# uStar.net
KiCad netlist of a schematic drawn in EAGLE
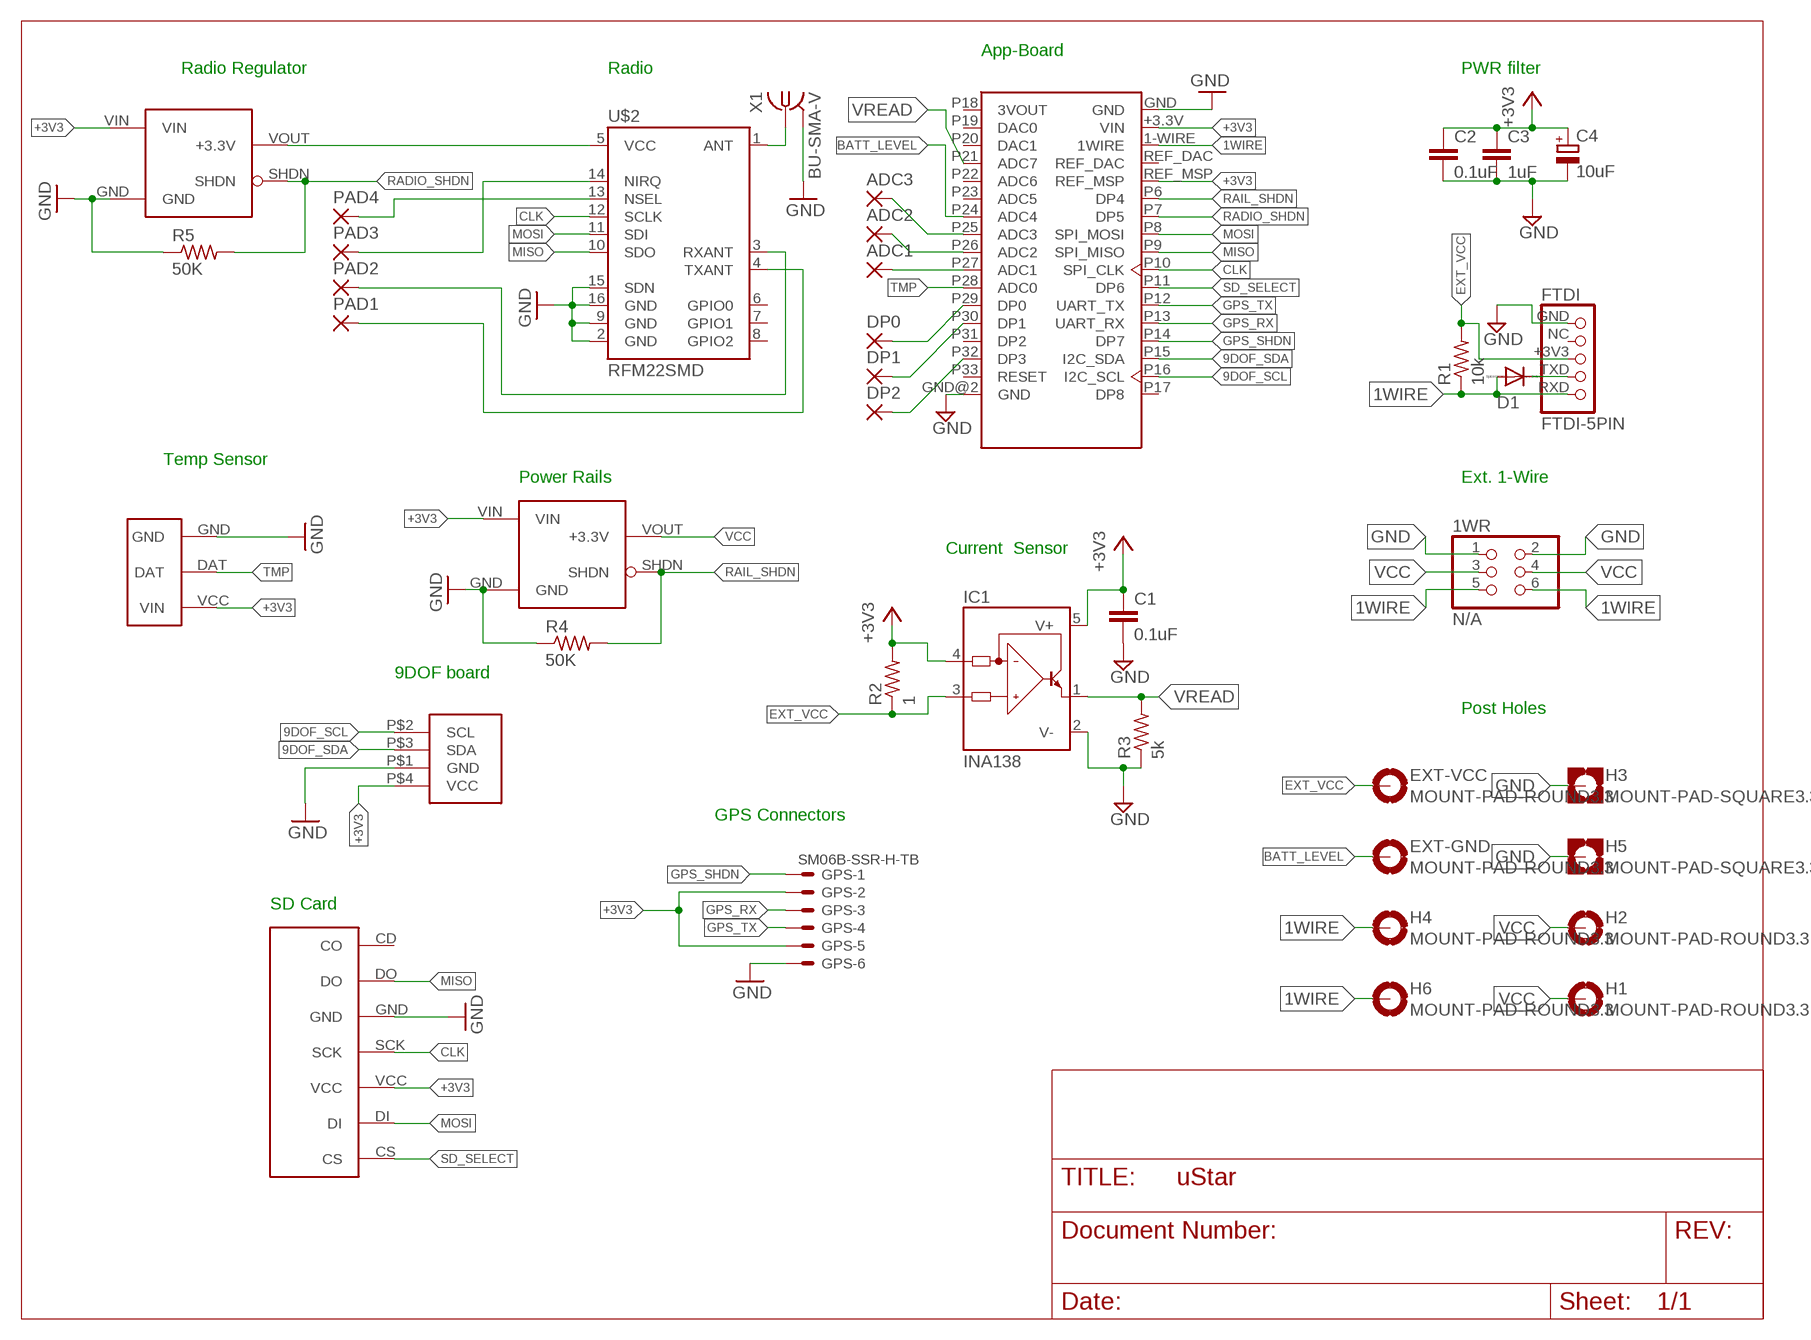
[diagram p0: schematic, sheet 1]

(export (version "E")
  (design (tool "Eeschema 10.0.6"))
  (components
    (comp (ref "1WR")
      (value "N/A")
      (footprint "eagle-import:2X03")
      (libsource (lib "eagle-import") (part "PINHD-2X3"))
    )
    (comp (ref "ADC1")
      (value "1,6/0,9")
      (footprint "eagle-import:1,6_0,9")
      (libsource (lib "eagle-import") (part "1,6/0,9"))
    )
    (comp (ref "ADC2")
      (value "1,6/0,9")
      (footprint "eagle-import:1,6_0,9")
      (libsource (lib "eagle-import") (part "1,6/0,9"))
    )
    (comp (ref "ADC3")
      (value "1,6/0,9")
      (footprint "eagle-import:1,6_0,9")
      (libsource (lib "eagle-import") (part "1,6/0,9"))
    )
    (comp (ref "C1")
      (value "0.1uF")
      (footprint "eagle-import:C0805")
      (libsource (lib "eagle-import") (part "C-EUC0805"))
    )
    (comp (ref "C2")
      (value "0.1uF")
      (footprint "eagle-import:C0603")
      (libsource (lib "eagle-import") (part "C-EUC0603"))
    )
    (comp (ref "C3")
      (value "1uF")
      (footprint "eagle-import:C0603")
      (libsource (lib "eagle-import") (part "C-EUC0603"))
    )
    (comp (ref "C4")
      (value "10uF")
      (footprint "eagle-import:SMC_B")
      (libsource (lib "eagle-import") (part "CPOL-EUSMCB"))
    )
    (comp (ref "D1")
      (value "1N4148DO35-7")
      (footprint "eagle-import:DO35-7")
      (libsource (lib "eagle-import") (part "1N4148DO35-7"))
    )
    (comp (ref "DP0")
      (value "1,6/0,9")
      (footprint "eagle-import:1,6_0,9")
      (libsource (lib "eagle-import") (part "1,6/0,9"))
    )
    (comp (ref "DP1")
      (value "1,6/0,9")
      (footprint "eagle-import:1,6_0,9")
      (libsource (lib "eagle-import") (part "1,6/0,9"))
    )
    (comp (ref "DP2")
      (value "1,6/0,9")
      (footprint "eagle-import:1,6_0,9")
      (libsource (lib "eagle-import") (part "1,6/0,9"))
    )
    (comp (ref "EXT-GND")
      (value "MOUNT-PAD-ROUND3.3")
      (footprint "eagle-import:3,3-PAD")
      (libsource (lib "eagle-import") (part "MOUNT-PAD-ROUND3.3"))
    )
    (comp (ref "EXT-VCC")
      (value "MOUNT-PAD-ROUND3.3")
      (footprint "eagle-import:3,3-PAD")
      (libsource (lib "eagle-import") (part "MOUNT-PAD-ROUND3.3"))
    )
    (comp (ref "FTDI")
      (value "FTDI-5PIN")
      (footprint "eagle-import:1_05X2MM")
      (libsource (lib "eagle-import") (part "FTDI-5PIN"))
    )
    (comp (ref "GPS")
      (value "SM06B-SSR-H-TB")
      (footprint "eagle-import:SM06B-SSR-H-TB")
      (libsource (lib "eagle-import") (part "SM06B-SSR-H-TB"))
    )
    (comp (ref "H1")
      (value "MOUNT-PAD-ROUND3.3")
      (footprint "eagle-import:3,3-PAD")
      (libsource (lib "eagle-import") (part "MOUNT-PAD-ROUND3.3"))
    )
    (comp (ref "H2")
      (value "MOUNT-PAD-ROUND3.3")
      (footprint "eagle-import:3,3-PAD")
      (libsource (lib "eagle-import") (part "MOUNT-PAD-ROUND3.3"))
    )
    (comp (ref "H3")
      (value "MOUNT-PAD-SQUARE3.3")
      (footprint "eagle-import:3,3-PAD-SQUARE")
      (libsource (lib "eagle-import") (part "MOUNT-PAD-SQUARE3.3"))
    )
    (comp (ref "H4")
      (value "MOUNT-PAD-ROUND3.3")
      (footprint "eagle-import:3,3-PAD")
      (libsource (lib "eagle-import") (part "MOUNT-PAD-ROUND3.3"))
    )
    (comp (ref "H5")
      (value "MOUNT-PAD-SQUARE3.3")
      (footprint "eagle-import:3,3-PAD-SQUARE")
      (libsource (lib "eagle-import") (part "MOUNT-PAD-SQUARE3.3"))
    )
    (comp (ref "H6")
      (value "MOUNT-PAD-ROUND3.3")
      (footprint "eagle-import:3,3-PAD")
      (libsource (lib "eagle-import") (part "MOUNT-PAD-ROUND3.3"))
    )
    (comp (ref "IC1")
      (value "INA138")
      (footprint "eagle-import:SOT23-5")
      (fields (field (name "MF") "TEXAS INSTRUMENTS") (field (name "MPN") "INA138NA/250"))
      (libsource (lib "eagle-import") (part "INA138"))
    )
    (comp (ref "PAD1")
      (value "1,6/0,9")
      (footprint "eagle-import:1,6_0,9")
      (libsource (lib "eagle-import") (part "1,6/0,9"))
    )
    (comp (ref "PAD2")
      (value "1,6/0,9")
      (footprint "eagle-import:1,6_0,9")
      (libsource (lib "eagle-import") (part "1,6/0,9"))
    )
    (comp (ref "PAD3")
      (value "1,6/0,9")
      (footprint "eagle-import:1,6_0,9")
      (libsource (lib "eagle-import") (part "1,6/0,9"))
    )
    (comp (ref "PAD4")
      (value "1,6/0,9")
      (footprint "eagle-import:1,6_0,9")
      (libsource (lib "eagle-import") (part "1,6/0,9"))
    )
    (comp (ref "R1")
      (value "10k")
      (footprint "eagle-import:0207_7")
      (libsource (lib "eagle-import") (part "resistor_R-US_0207/7"))
    )
    (comp (ref "R2")
      (value "1")
      (footprint "eagle-import:R0603")
      (libsource (lib "eagle-import") (part "resistor_R-US_R0603"))
    )
    (comp (ref "R3")
      (value "5k")
      (footprint "eagle-import:R0603")
      (libsource (lib "eagle-import") (part "resistor_R-US_R0603"))
    )
    (comp (ref "R4")
      (value "50K")
      (footprint "eagle-import:R0603")
      (libsource (lib "eagle-import") (part "R-US_R0603"))
    )
    (comp (ref "R5")
      (value "50K")
      (footprint "eagle-import:R0603")
      (libsource (lib "eagle-import") (part "R-US_R0603"))
    )
    (comp (ref "U$1")
      (value "App-Board 1.2/1.3")
      (footprint "eagle-import:APPCORE_RECEIVER")
      (libsource (lib "eagle-import") (part "APP_CORE"))
    )
    (comp (ref "U$2")
      (value "RFM22SMD")
      (footprint "eagle-import:RFM22-XXX-S2")
      (libsource (lib "eagle-import") (part "RFM22SMD"))
    )
    (comp (ref "U$3")
      (value "S7V8F3_VOLT_REG-3V3_1AHORZ-DOWN")
      (footprint "eagle-import:S7V_DOWN")
      (libsource (lib "eagle-import") (part "S7V8F3_VOLT_REG-3V3_1AHORZ-DOWN"))
    )
    (comp (ref "U$4")
      (value "TMP_EXT")
      (footprint "eagle-import:TMP_EXT")
      (libsource (lib "eagle-import") (part "TMP_EXT"))
    )
    (comp (ref "U$5")
      (value "9DOF")
      (footprint "eagle-import:9DOF")
      (libsource (lib "eagle-import") (part "9DOF"))
    )
    (comp (ref "U$6")
      (value "SDCARD_EXT")
      (footprint "eagle-import:SDCARD_EXT")
      (libsource (lib "eagle-import") (part "SDCARD_EXT"))
    )
    (comp (ref "U$7")
      (value "S7V8F3_VOLT_REG-3V3_1AHORZ-DOWN")
      (footprint "eagle-import:S7V_DOWN")
      (libsource (lib "eagle-import") (part "S7V8F3_VOLT_REG-3V3_1AHORZ-DOWN"))
    )
    (comp (ref "X1")
      (value "BU-SMA-V")
      (footprint "eagle-import:BU-SMA-V")
      (libsource (lib "eagle-import") (part "BU-SMA-V"))
    )
  )
  (nets
    (net (code "1") (name "+3V3") (class "Default")
      (node (ref "C1") (pin "1") (pinfunction "1_1") (pintype "passive"))
      (node (ref "C2") (pin "1") (pinfunction "1_1") (pintype "passive"))
      (node (ref "C3") (pin "1") (pinfunction "1_1") (pintype "passive"))
      (node (ref "C4") (pin "+") (pinfunction "+_+") (pintype "passive"))
      (node (ref "GPS") (pin "2") (pinfunction "S_2") (pintype "passive"))
      (node (ref "GPS") (pin "5") (pinfunction "S_5") (pintype "passive"))
      (node (ref "IC1") (pin "4") (pinfunction "IN-_4") (pintype "input"))
      (node (ref "IC1") (pin "5") (pinfunction "V+_5") (pintype "power_in"))
      (node (ref "R2") (pin "2") (pinfunction "2_2") (pintype "passive"))
      (node (ref "U$1") (pin "+3.3V") (pinfunction "VIN_+3.3V") (pintype "power_in"))
      (node (ref "U$1") (pin "REF_MSP") (pinfunction "REF_MSP_REF_MSP") (pintype "input"))
      (node (ref "U$3") (pin "VIN") (pinfunction "VIN_VIN") (pintype "power_in"))
      (node (ref "U$4") (pin "VCC") (pinfunction "VIN_VCC") (pintype "bidirectional"))
      (node (ref "U$5") (pin "P$4") (pinfunction "VCC_P$4") (pintype "bidirectional"))
      (node (ref "U$6") (pin "VCC") (pinfunction "VCC_VCC") (pintype "bidirectional"))
      (node (ref "U$7") (pin "VIN") (pinfunction "VIN_VIN") (pintype "power_in"))
    )
    (net (code "2") (name "1WIRE") (class "Default")
      (node (ref "1WR") (pin "5") (pinfunction "5_5") (pintype "passive"))
      (node (ref "1WR") (pin "6") (pinfunction "6_6") (pintype "passive"))
      (node (ref "D1") (pin "A") (pinfunction "A_A") (pintype "passive"))
      (node (ref "FTDI") (pin "RXD") (pinfunction "RXD_RXD") (pintype "input"))
      (node (ref "H4") (pin "B3,3") (pinfunction "MOUNT_B3,3") (pintype "passive"))
      (node (ref "H6") (pin "B3,3") (pinfunction "MOUNT_B3,3") (pintype "passive"))
      (node (ref "R1") (pin "1") (pinfunction "1_1") (pintype "passive"))
      (node (ref "U$1") (pin "1-WIRE") (pinfunction "1WIRE_1-WIRE") (pintype "bidirectional"))
    )
    (net (code "3") (name "9DOF_SCL") (class "Default")
      (node (ref "U$1") (pin "P16") (pinfunction "I2C_SCL_P16") (pintype "bidirectional"))
      (node (ref "U$5") (pin "P$2") (pinfunction "SCL_P$2") (pintype "bidirectional"))
    )
    (net (code "4") (name "9DOF_SDA") (class "Default")
      (node (ref "U$1") (pin "P15") (pinfunction "I2C_SDA_P15") (pintype "bidirectional"))
      (node (ref "U$5") (pin "P$3") (pinfunction "SDA_P$3") (pintype "bidirectional"))
    )
    (net (code "5") (name "BATT_LEVEL") (class "Default")
      (node (ref "EXT-GND") (pin "B3,3") (pinfunction "MOUNT_B3,3") (pintype "passive"))
      (node (ref "U$1") (pin "P24") (pinfunction "ADC4_P24") (pintype "input"))
    )
    (net (code "6") (name "CLK") (class "Default")
      (node (ref "U$1") (pin "P10") (pinfunction "SPI_CLK_P10") (pintype "bidirectional"))
      (node (ref "U$2") (pin "12") (pinfunction "SCLK_12") (pintype "input"))
      (node (ref "U$6") (pin "SCK") (pinfunction "SCK_SCK") (pintype "bidirectional"))
    )
    (net (code "7") (name "EXT_VCC") (class "Default")
      (node (ref "EXT-VCC") (pin "B3,3") (pinfunction "MOUNT_B3,3") (pintype "passive"))
      (node (ref "FTDI") (pin "+3V3") (pinfunction "+3V3_+3V3") (pintype "power_in"))
      (node (ref "IC1") (pin "3") (pinfunction "IN+_3") (pintype "input"))
      (node (ref "R1") (pin "2") (pinfunction "2_2") (pintype "passive"))
      (node (ref "R2") (pin "1") (pinfunction "1_1") (pintype "passive"))
    )
    (net (code "8") (name "GND") (class "Default")
      (node (ref "1WR") (pin "1") (pinfunction "1_1") (pintype "passive"))
      (node (ref "1WR") (pin "2") (pinfunction "2_2") (pintype "passive"))
      (node (ref "C1") (pin "2") (pinfunction "2_2") (pintype "passive"))
      (node (ref "C2") (pin "2") (pinfunction "2_2") (pintype "passive"))
      (node (ref "C3") (pin "2") (pinfunction "2_2") (pintype "passive"))
      (node (ref "C4") (pin "-") (pinfunction "-_-") (pintype "passive"))
      (node (ref "FTDI") (pin "GND") (pinfunction "GND_GND") (pintype "power_in"))
      (node (ref "GPS") (pin "6") (pinfunction "S_6") (pintype "passive"))
      (node (ref "H3") (pin "B3,3") (pinfunction "MOUNT_B3,3") (pintype "passive"))
      (node (ref "H5") (pin "B3,3") (pinfunction "MOUNT_B3,3") (pintype "passive"))
      (node (ref "IC1") (pin "2") (pinfunction "V-_2") (pintype "power_in"))
      (node (ref "R3") (pin "1") (pinfunction "1_1") (pintype "passive"))
      (node (ref "R4") (pin "1") (pinfunction "1_1") (pintype "passive"))
      (node (ref "R5") (pin "1") (pinfunction "1_1") (pintype "passive"))
      (node (ref "U$1") (pin "GND") (pinfunction "GND_GND") (pintype "power_in"))
      (node (ref "U$1") (pin "GND@2") (pinfunction "GND_GND@2") (pintype "power_in"))
      (node (ref "U$2") (pin "15") (pinfunction "SDN_15") (pintype "input"))
      (node (ref "U$2") (pin "16") (pinfunction "GND_16") (pintype "power_in"))
      (node (ref "U$2") (pin "2") (pinfunction "GND_2") (pintype "power_in"))
      (node (ref "U$2") (pin "9") (pinfunction "GND_9") (pintype "power_in"))
      (node (ref "U$3") (pin "GND") (pinfunction "GND_GND") (pintype "power_in"))
      (node (ref "U$4") (pin "GND") (pinfunction "GND_GND") (pintype "bidirectional"))
      (node (ref "U$5") (pin "P$1") (pinfunction "GND_P$1") (pintype "bidirectional"))
      (node (ref "U$6") (pin "GND") (pinfunction "GND_GND") (pintype "bidirectional"))
      (node (ref "U$7") (pin "GND") (pinfunction "GND_GND") (pintype "power_in"))
      (node (ref "X1") (pin "2") (pinfunction "2_2") (pintype "passive"))
      (node (ref "X1") (pin "3") (pinfunction "2_3") (pintype "passive"))
      (node (ref "X1") (pin "4") (pinfunction "2_4") (pintype "passive"))
      (node (ref "X1") (pin "5") (pinfunction "2_5") (pintype "passive"))
    )
    (net (code "9") (name "GPS_RX") (class "Default")
      (node (ref "GPS") (pin "3") (pinfunction "S_3") (pintype "passive"))
      (node (ref "U$1") (pin "P13") (pinfunction "UART_RX_P13") (pintype "input"))
    )
    (net (code "10") (name "GPS_SHDN") (class "Default")
      (node (ref "GPS") (pin "1") (pinfunction "S_1") (pintype "passive"))
      (node (ref "U$1") (pin "P14") (pinfunction "DP7_P14") (pintype "bidirectional"))
    )
    (net (code "11") (name "GPS_TX") (class "Default")
      (node (ref "GPS") (pin "4") (pinfunction "S_4") (pintype "passive"))
      (node (ref "U$1") (pin "P12") (pinfunction "UART_TX_P12") (pintype "output"))
    )
    (net (code "12") (name "MISO") (class "Default")
      (node (ref "U$1") (pin "P9") (pinfunction "SPI_MISO_P9") (pintype "bidirectional"))
      (node (ref "U$2") (pin "10") (pinfunction "SDO_10") (pintype "output"))
      (node (ref "U$6") (pin "DO") (pinfunction "DO_DO") (pintype "bidirectional"))
    )
    (net (code "13") (name "MOSI") (class "Default")
      (node (ref "U$1") (pin "P8") (pinfunction "SPI_MOSI_P8") (pintype "bidirectional"))
      (node (ref "U$2") (pin "11") (pinfunction "SDI_11") (pintype "input"))
      (node (ref "U$6") (pin "DI") (pinfunction "DI_DI") (pintype "bidirectional"))
    )
    (net (code "14") (name "Net-(ADC1-P)") (class "Default")
      (node (ref "ADC1") (pin "1") (pinfunction "P_1") (pintype "passive"))
      (node (ref "U$1") (pin "P27") (pinfunction "ADC1_P27") (pintype "input"))
    )
    (net (code "15") (name "Net-(ADC2-P)") (class "Default")
      (node (ref "ADC2") (pin "1") (pinfunction "P_1") (pintype "passive"))
      (node (ref "U$1") (pin "P26") (pinfunction "ADC2_P26") (pintype "input"))
    )
    (net (code "16") (name "Net-(ADC3-P)") (class "Default")
      (node (ref "ADC3") (pin "1") (pinfunction "P_1") (pintype "passive"))
      (node (ref "U$1") (pin "P25") (pinfunction "ADC3_P25") (pintype "input"))
    )
    (net (code "17") (name "Net-(D1-PadC)") (class "Default")
      (node (ref "D1") (pin "C") (pinfunction "C_C") (pintype "passive"))
      (node (ref "FTDI") (pin "TXD") (pinfunction "TXD_TXD") (pintype "output"))
    )
    (net (code "18") (name "Net-(DP0-P)") (class "Default")
      (node (ref "DP0") (pin "1") (pinfunction "P_1") (pintype "passive"))
      (node (ref "U$1") (pin "P29") (pinfunction "DP0_P29") (pintype "bidirectional"))
    )
    (net (code "19") (name "Net-(DP1-P)") (class "Default")
      (node (ref "DP1") (pin "1") (pinfunction "P_1") (pintype "passive"))
      (node (ref "U$1") (pin "P30") (pinfunction "DP1_P30") (pintype "bidirectional"))
    )
    (net (code "20") (name "Net-(DP2-P)") (class "Default")
      (node (ref "DP2") (pin "1") (pinfunction "P_1") (pintype "passive"))
      (node (ref "U$1") (pin "P32") (pinfunction "DP3_P32") (pintype "bidirectional"))
    )
    (net (code "21") (name "Net-(PAD1-P)") (class "Default")
      (node (ref "PAD1") (pin "1") (pinfunction "P_1") (pintype "passive"))
      (node (ref "U$2") (pin "4") (pinfunction "TXANT_4") (pintype "input"))
    )
    (net (code "22") (name "Net-(PAD2-P)") (class "Default")
      (node (ref "PAD2") (pin "1") (pinfunction "P_1") (pintype "passive"))
      (node (ref "U$2") (pin "3") (pinfunction "RXANT_3") (pintype "input"))
    )
    (net (code "23") (name "Net-(PAD3-P)") (class "Default")
      (node (ref "PAD3") (pin "1") (pinfunction "P_1") (pintype "passive"))
      (node (ref "U$2") (pin "14") (pinfunction "NIRQ_14") (pintype "output"))
    )
    (net (code "24") (name "Net-(PAD4-P)") (class "Default")
      (node (ref "PAD4") (pin "1") (pinfunction "P_1") (pintype "passive"))
      (node (ref "U$2") (pin "13") (pinfunction "NSEL_13") (pintype "input"))
    )
    (net (code "25") (name "Net-(U$2-ANT)") (class "Default")
      (node (ref "U$2") (pin "1") (pinfunction "ANT_1") (pintype "bidirectional"))
      (node (ref "X1") (pin "1") (pinfunction "1_1") (pintype "passive"))
    )
    (net (code "26") (name "Net-(U$2-VCC)") (class "Default")
      (node (ref "U$2") (pin "5") (pinfunction "VCC_5") (pintype "bidirectional"))
      (node (ref "U$3") (pin "VOUT") (pinfunction "+3.3V_VOUT") (pintype "output"))
    )
    (net (code "27") (name "RADIO_SHDN") (class "Default")
      (node (ref "R5") (pin "2") (pinfunction "2_2") (pintype "passive"))
      (node (ref "U$1") (pin "P7") (pinfunction "DP5_P7") (pintype "bidirectional"))
      (node (ref "U$3") (pin "SHDN") (pinfunction "SHDN_SHDN") (pintype "input"))
    )
    (net (code "28") (name "RAIL_SHDN") (class "Default")
      (node (ref "R4") (pin "2") (pinfunction "2_2") (pintype "passive"))
      (node (ref "U$1") (pin "P6") (pinfunction "DP4_P6") (pintype "bidirectional"))
      (node (ref "U$7") (pin "SHDN") (pinfunction "SHDN_SHDN") (pintype "input"))
    )
    (net (code "29") (name "SD_SELECT") (class "Default")
      (node (ref "U$1") (pin "P11") (pinfunction "DP6_P11") (pintype "bidirectional"))
      (node (ref "U$6") (pin "CS") (pinfunction "CS_CS") (pintype "bidirectional"))
    )
    (net (code "30") (name "TMP") (class "Default")
      (node (ref "U$1") (pin "P28") (pinfunction "ADC0_P28") (pintype "input"))
      (node (ref "U$4") (pin "DAT") (pinfunction "DAT_DAT") (pintype "bidirectional"))
    )
    (net (code "31") (name "VCC") (class "Default")
      (node (ref "1WR") (pin "3") (pinfunction "3_3") (pintype "passive"))
      (node (ref "1WR") (pin "4") (pinfunction "4_4") (pintype "passive"))
      (node (ref "H1") (pin "B3,3") (pinfunction "MOUNT_B3,3") (pintype "passive"))
      (node (ref "H2") (pin "B3,3") (pinfunction "MOUNT_B3,3") (pintype "passive"))
      (node (ref "U$7") (pin "VOUT") (pinfunction "+3.3V_VOUT") (pintype "output"))
    )
    (net (code "32") (name "VREAD") (class "Default")
      (node (ref "IC1") (pin "1") (pinfunction "OUT_1") (pintype "output"))
      (node (ref "R3") (pin "2") (pinfunction "2_2") (pintype "passive"))
      (node (ref "U$1") (pin "P21") (pinfunction "ADC7_P21") (pintype "input"))
    )
    (net (code "33") (name "unconnected-(FTDI-PadNC)") (class "Default")
      (node (ref "FTDI") (pin "NC") (pinfunction "NC_NC") (pintype "no_connect"))
    )
    (net (code "34") (name "unconnected-(U$1-3VOUT-PadP18)") (class "Default")
      (node (ref "U$1") (pin "P18") (pinfunction "3VOUT_P18") (pintype "output"))
    )
    (net (code "35") (name "unconnected-(U$1-ADC5-PadP23)") (class "Default")
      (node (ref "U$1") (pin "P23") (pinfunction "ADC5_P23") (pintype "input"))
    )
    (net (code "36") (name "unconnected-(U$1-ADC6-PadP22)") (class "Default")
      (node (ref "U$1") (pin "P22") (pinfunction "ADC6_P22") (pintype "input"))
    )
    (net (code "37") (name "unconnected-(U$1-DAC0-PadP19)") (class "Default")
      (node (ref "U$1") (pin "P19") (pinfunction "DAC0_P19") (pintype "bidirectional"))
    )
    (net (code "38") (name "unconnected-(U$1-DAC1-PadP20)") (class "Default")
      (node (ref "U$1") (pin "P20") (pinfunction "DAC1_P20") (pintype "bidirectional"))
    )
    (net (code "39") (name "unconnected-(U$1-DP2-PadP31)") (class "Default")
      (node (ref "U$1") (pin "P31") (pinfunction "DP2_P31") (pintype "bidirectional"))
    )
    (net (code "40") (name "unconnected-(U$1-DP8-PadP17)") (class "Default")
      (node (ref "U$1") (pin "P17") (pinfunction "DP8_P17") (pintype "bidirectional"))
    )
    (net (code "41") (name "unconnected-(U$1-PadREF_DAC)") (class "Default")
      (node (ref "U$1") (pin "REF_DAC") (pinfunction "REF_DAC_REF_DAC") (pintype "input"))
    )
    (net (code "42") (name "unconnected-(U$1-RESET-PadP33)") (class "Default")
      (node (ref "U$1") (pin "P33") (pinfunction "RESET_P33") (pintype "bidirectional"))
    )
    (net (code "43") (name "unconnected-(U$2-GPIO0-Pad6)") (class "Default")
      (node (ref "U$2") (pin "6") (pinfunction "GPIO0_6") (pintype "bidirectional"))
    )
    (net (code "44") (name "unconnected-(U$2-GPIO1-Pad7)") (class "Default")
      (node (ref "U$2") (pin "7") (pinfunction "GPIO1_7") (pintype "bidirectional"))
    )
    (net (code "45") (name "unconnected-(U$2-GPIO2-Pad8)") (class "Default")
      (node (ref "U$2") (pin "8") (pinfunction "GPIO2_8") (pintype "bidirectional"))
    )
    (net (code "46") (name "unconnected-(U$6-CO-PadCD)") (class "Default")
      (node (ref "U$6") (pin "CD") (pinfunction "CO_CD") (pintype "bidirectional"))
    )
  )
)
